# 05_LMS7002M_Misc.net
KiCad netlist of a schematic drawn in Altium Designer
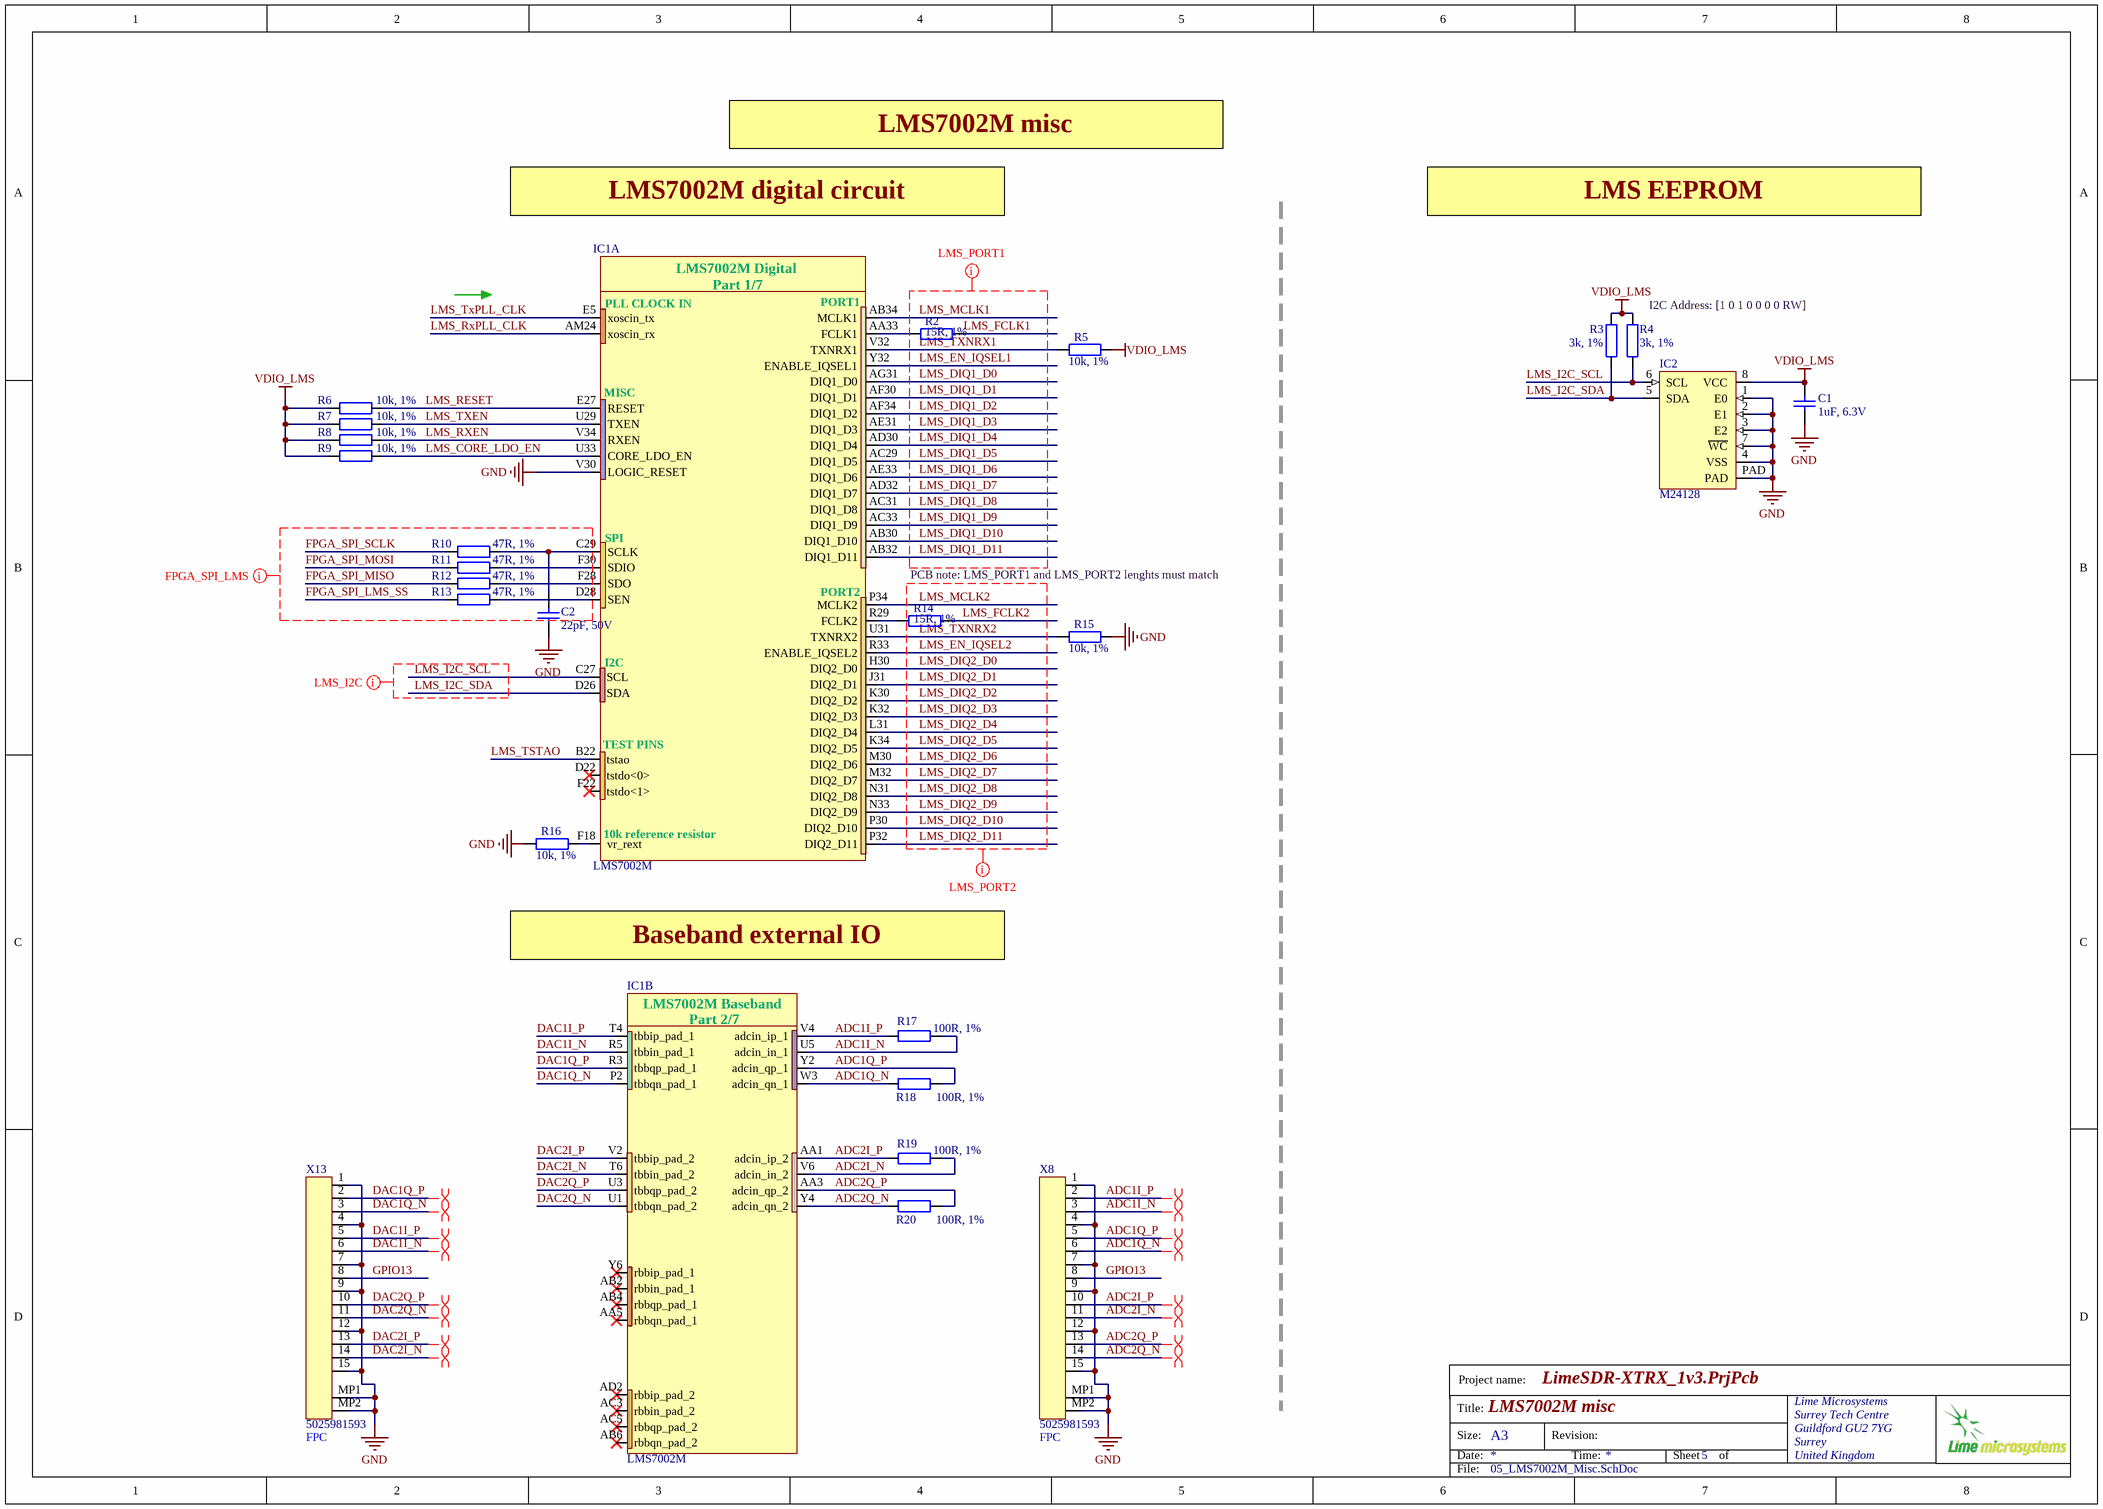
[diagram p0: 05_LMS7002M_Misc.SchDoc]

(export (version "E")
  (design (tool "Eeschema 10.0.6"))
  (components
    (comp (ref "C1")
      (value "1uF, 6.3V")
      (footprint "CAP0201")
      (fields (field (name "TOLERANCE") "±20%") (field (name "MANUFACTURER") "TDK Corporation"))
      (libsource (lib "LimeMicroAltiumLib_schLib") (part "Cap_0402"))
    )
    (comp (ref "C2")
      (value "22pF, 50V")
      (footprint "CAP0201")
      (fields
        (field (name "MANUFACTURER") "Murata")
        (field (name "TOLERANCE") "5%")
        (field (name "VOLTAGE") "50V")
      )
      (libsource (lib "LimeMicroAltiumLib_schLib") (part "Cap_0402"))
    )
    (comp (ref "IC1")
      (value "LMS7002M")
      (footprint "LMS7002M_v5_LESS_SILK")
      (description "Schematic symbol revision 4. Default footprint - 0.31mm pad")
      (fields (field (name "MANUFACTURER") "Lime Microsystems"))
      (libsource (lib "LimeMicroAltiumLib_schLib_r04") (part "LMS7002Mr4"))
    )
    (comp (ref "IC2")
      (value "M24128")
      (footprint "M24128-DFMC6TG")
      (fields (field (name "MANUFACTURER") "STMicroelectronics"))
      (libsource (lib "LimeMicroAltiumLib_schLib") (part "M24128-DFMC6TG"))
    )
    (comp (ref "R2")
      (value "15R, 1%")
      (footprint "RES0201")
      (fields (field (name "MANUFACTURER") "Yageo") (field (name "TOLERANCE") "1%"))
      (libsource (lib "LimeFPGAboard_schLib") (part "Res_0402"))
    )
    (comp (ref "R3")
      (value "3k, 1%")
      (footprint "RES0201")
      (fields (field (name "MANUFACTURER") "Yageo") (field (name "TOLERANCE") "1%"))
      (libsource (lib "LimeFPGAboard_schLib") (part "Res_0402"))
    )
    (comp (ref "R4")
      (value "3k, 1%")
      (footprint "RES0201")
      (fields (field (name "MANUFACTURER") "Yageo") (field (name "TOLERANCE") "1%"))
      (libsource (lib "LimeFPGAboard_schLib") (part "Res_0402"))
    )
    (comp (ref "R5")
      (value "10k, 1%")
      (footprint "RES0201")
      (fields (field (name "MANUFACTURER") "Yageo") (field (name "TOLERANCE") "1%"))
      (libsource (lib "LimeFPGAboard_schLib") (part "Res_0402"))
    )
    (comp (ref "R6")
      (value "10k, 1%")
      (footprint "RES0201")
      (fields (field (name "MANUFACTURER") "Yageo") (field (name "TOLERANCE") "1%"))
      (libsource (lib "LimeFPGAboard_schLib") (part "Res_0402"))
    )
    (comp (ref "R7")
      (value "10k, 1%")
      (footprint "RES0201")
      (fields (field (name "MANUFACTURER") "Yageo") (field (name "TOLERANCE") "1%"))
      (libsource (lib "LimeFPGAboard_schLib") (part "Res_0402"))
    )
    (comp (ref "R8")
      (value "10k, 1%")
      (footprint "RES0201")
      (fields (field (name "MANUFACTURER") "Yageo") (field (name "TOLERANCE") "1%"))
      (libsource (lib "LimeFPGAboard_schLib") (part "Res_0402"))
    )
    (comp (ref "R9")
      (value "10k, 1%")
      (footprint "RES0201")
      (fields (field (name "MANUFACTURER") "Yageo") (field (name "TOLERANCE") "1%"))
      (libsource (lib "LimeFPGAboard_schLib") (part "Res_0402"))
    )
    (comp (ref "R10")
      (value "47R, 1%")
      (footprint "RES0201")
      (fields (field (name "MANUFACTURER") "Yageo") (field (name "TOLERANCE") "1%"))
      (libsource (lib "LimeFPGAboard_schLib") (part "Res_0402"))
    )
    (comp (ref "R11")
      (value "47R, 1%")
      (footprint "RES0201")
      (fields (field (name "MANUFACTURER") "Yageo") (field (name "TOLERANCE") "1%"))
      (libsource (lib "LimeFPGAboard_schLib") (part "Res_0402"))
    )
    (comp (ref "R12")
      (value "47R, 1%")
      (footprint "RES0201")
      (fields (field (name "MANUFACTURER") "Yageo") (field (name "TOLERANCE") "1%"))
      (libsource (lib "LimeFPGAboard_schLib") (part "Res_0402"))
    )
    (comp (ref "R13")
      (value "47R, 1%")
      (footprint "RES0201")
      (fields (field (name "MANUFACTURER") "Yageo") (field (name "TOLERANCE") "1%"))
      (libsource (lib "LimeFPGAboard_schLib") (part "Res_0402"))
    )
    (comp (ref "R14")
      (value "15R, 1%")
      (footprint "RES0201")
      (fields (field (name "MANUFACTURER") "Yageo") (field (name "TOLERANCE") "1%"))
      (libsource (lib "LimeFPGAboard_schLib") (part "Res_0402"))
    )
    (comp (ref "R15")
      (value "10k, 1%")
      (footprint "RES0201")
      (fields (field (name "MANUFACTURER") "Yageo") (field (name "TOLERANCE") "1%"))
      (libsource (lib "LimeFPGAboard_schLib") (part "Res_0402"))
    )
    (comp (ref "R16")
      (value "10k, 1%")
      (footprint "RES0201")
      (fields (field (name "MANUFACTURER") "Yageo") (field (name "TOLERANCE") "1%"))
      (libsource (lib "LimeFPGAboard_schLib") (part "Res_0402"))
    )
    (comp (ref "R17")
      (value "100R, 1%")
      (footprint "RES0201")
      (fields (field (name "MANUFACTURER") "Yageo") (field (name "TOLERANCE") "1%"))
      (libsource (lib "LimeFPGAboard_schLib") (part "Res_0402"))
    )
    (comp (ref "R18")
      (value "100R, 1%")
      (footprint "RES0201")
      (fields (field (name "MANUFACTURER") "Yageo") (field (name "TOLERANCE") "1%"))
      (libsource (lib "LimeFPGAboard_schLib") (part "Res_0402"))
    )
    (comp (ref "R19")
      (value "100R, 1%")
      (footprint "RES0201")
      (fields (field (name "MANUFACTURER") "Yageo") (field (name "TOLERANCE") "1%"))
      (libsource (lib "LimeFPGAboard_schLib") (part "Res_0402"))
    )
    (comp (ref "R20")
      (value "100R, 1%")
      (footprint "RES0201")
      (fields (field (name "MANUFACTURER") "Yageo") (field (name "TOLERANCE") "1%"))
      (libsource (lib "LimeFPGAboard_schLib") (part "Res_0402"))
    )
    (comp (ref "X8")
      (value "5025981593")
      (footprint "5025981593_FPC_connector")
      (fields (field (name "MANUFACTURER") "Molex"))
      (libsource (lib "LimeMicroAltiumLib_schLib_r04") (part "5025981593_FPC_connector"))
    )
    (comp (ref "X13")
      (value "5025981593")
      (footprint "5025981593_FPC_connector")
      (fields (field (name "MANUFACTURER") "Molex"))
      (libsource (lib "LimeMicroAltiumLib_schLib_r04") (part "5025981593_FPC_connector"))
    )
  )
  (nets
    (net (code "1") (name "/ADC1I_N") (class "Default")
      (node (ref "IC1") (pin "U5") (pinfunction "adcin_in_1_U5") (pintype "passive"))
      (node (ref "R17") (pin "2") (pinfunction "2_2") (pintype "passive"))
      (node (ref "X8") (pin "3") (pinfunction "3_3") (pintype "passive"))
    )
    (net (code "2") (name "/ADC1I_P") (class "Default")
      (node (ref "IC1") (pin "V4") (pinfunction "adcin_ip_1_V4") (pintype "passive"))
      (node (ref "R17") (pin "1") (pinfunction "1_1") (pintype "passive"))
      (node (ref "X8") (pin "2") (pinfunction "2_2") (pintype "passive"))
    )
    (net (code "3") (name "/ADC1Q_N") (class "Default")
      (node (ref "IC1") (pin "W3") (pinfunction "adcin_qn_1_W3") (pintype "passive"))
      (node (ref "R18") (pin "1") (pinfunction "1_1") (pintype "passive"))
      (node (ref "X8") (pin "6") (pinfunction "6_6") (pintype "passive"))
    )
    (net (code "4") (name "/ADC1Q_P") (class "Default")
      (node (ref "IC1") (pin "Y2") (pinfunction "adcin_qp_1_Y2") (pintype "passive"))
      (node (ref "R18") (pin "2") (pinfunction "2_2") (pintype "passive"))
      (node (ref "X8") (pin "5") (pinfunction "5_5") (pintype "passive"))
    )
    (net (code "5") (name "/ADC2I_N") (class "Default")
      (node (ref "IC1") (pin "V6") (pinfunction "adcin_in_2_V6") (pintype "passive"))
      (node (ref "R19") (pin "2") (pinfunction "2_2") (pintype "passive"))
      (node (ref "X8") (pin "11") (pinfunction "11_11") (pintype "passive"))
    )
    (net (code "6") (name "/ADC2I_P") (class "Default")
      (node (ref "IC1") (pin "AA1") (pinfunction "adcin_ip_2_AA1") (pintype "passive"))
      (node (ref "R19") (pin "1") (pinfunction "1_1") (pintype "passive"))
      (node (ref "X8") (pin "10") (pinfunction "10_10") (pintype "passive"))
    )
    (net (code "7") (name "/ADC2Q_N") (class "Default")
      (node (ref "IC1") (pin "Y4") (pinfunction "adcin_qn_2_Y4") (pintype "passive"))
      (node (ref "R20") (pin "1") (pinfunction "1_1") (pintype "passive"))
      (node (ref "X8") (pin "14") (pinfunction "14_14") (pintype "passive"))
    )
    (net (code "8") (name "/ADC2Q_P") (class "Default")
      (node (ref "IC1") (pin "AA3") (pinfunction "adcin_qp_2_AA3") (pintype "passive"))
      (node (ref "R20") (pin "2") (pinfunction "2_2") (pintype "passive"))
      (node (ref "X8") (pin "13") (pinfunction "13_13") (pintype "passive"))
    )
    (net (code "9") (name "/DAC1I_N") (class "Default")
      (node (ref "IC1") (pin "R5") (pinfunction "tbbin_pad_1_R5") (pintype "passive"))
      (node (ref "X13") (pin "6") (pinfunction "6_6") (pintype "passive"))
    )
    (net (code "10") (name "/DAC1I_P") (class "Default")
      (node (ref "IC1") (pin "T4") (pinfunction "tbbip_pad_1_T4") (pintype "passive"))
      (node (ref "X13") (pin "5") (pinfunction "5_5") (pintype "passive"))
    )
    (net (code "11") (name "/DAC1Q_N") (class "Default")
      (node (ref "IC1") (pin "P2") (pinfunction "tbbqn_pad_1_P2") (pintype "passive"))
      (node (ref "X13") (pin "3") (pinfunction "3_3") (pintype "passive"))
    )
    (net (code "12") (name "/DAC1Q_P") (class "Default")
      (node (ref "IC1") (pin "R3") (pinfunction "tbbqp_pad_1_R3") (pintype "passive"))
      (node (ref "X13") (pin "2") (pinfunction "2_2") (pintype "passive"))
    )
    (net (code "13") (name "/DAC2I_N") (class "Default")
      (node (ref "IC1") (pin "T6") (pinfunction "tbbin_pad_2_T6") (pintype "passive"))
      (node (ref "X13") (pin "14") (pinfunction "14_14") (pintype "passive"))
    )
    (net (code "14") (name "/DAC2I_P") (class "Default")
      (node (ref "IC1") (pin "V2") (pinfunction "tbbip_pad_2_V2") (pintype "passive"))
      (node (ref "X13") (pin "13") (pinfunction "13_13") (pintype "passive"))
    )
    (net (code "15") (name "/DAC2Q_N") (class "Default")
      (node (ref "IC1") (pin "U1") (pinfunction "tbbqn_pad_2_U1") (pintype "passive"))
      (node (ref "X13") (pin "11") (pinfunction "11_11") (pintype "passive"))
    )
    (net (code "16") (name "/DAC2Q_P") (class "Default")
      (node (ref "IC1") (pin "U3") (pinfunction "tbbqp_pad_2_U3") (pintype "passive"))
      (node (ref "X13") (pin "10") (pinfunction "10_10") (pintype "passive"))
    )
    (net (code "17") (name "/FPGA_SPI_LMS_SS") (class "Default")
      (node (ref "R13") (pin "2") (pinfunction "2_2") (pintype "passive"))
    )
    (net (code "18") (name "/FPGA_SPI_MISO") (class "Default")
      (node (ref "R12") (pin "2") (pinfunction "2_2") (pintype "passive"))
    )
    (net (code "19") (name "/FPGA_SPI_MOSI") (class "Default")
      (node (ref "R11") (pin "2") (pinfunction "2_2") (pintype "passive"))
    )
    (net (code "20") (name "/FPGA_SPI_SCLK") (class "Default")
      (node (ref "R10") (pin "2") (pinfunction "2_2") (pintype "passive"))
    )
    (net (code "21") (name "/GPIO13") (class "Default")
      (node (ref "X13") (pin "8") (pinfunction "8_8") (pintype "passive"))
      (node (ref "X8") (pin "8") (pinfunction "8_8") (pintype "passive"))
    )
    (net (code "22") (name "/LMS_CORE_LDO_EN") (class "Default")
      (node (ref "IC1") (pin "U33") (pinfunction "CORE_LDO_EN_U33") (pintype "passive"))
      (node (ref "R9") (pin "1") (pinfunction "1_1") (pintype "passive"))
    )
    (net (code "23") (name "/LMS_DIQ1_D0") (class "Default")
      (node (ref "IC1") (pin "AG31") (pinfunction "DIQ1_D0_AG31") (pintype "passive"))
    )
    (net (code "24") (name "/LMS_DIQ1_D1") (class "Default")
      (node (ref "IC1") (pin "AF30") (pinfunction "DIQ1_D1_AF30") (pintype "passive"))
    )
    (net (code "25") (name "/LMS_DIQ1_D2") (class "Default")
      (node (ref "IC1") (pin "AF34") (pinfunction "DIQ1_D2_AF34") (pintype "passive"))
    )
    (net (code "26") (name "/LMS_DIQ1_D3") (class "Default")
      (node (ref "IC1") (pin "AE31") (pinfunction "DIQ1_D3_AE31") (pintype "passive"))
    )
    (net (code "27") (name "/LMS_DIQ1_D4") (class "Default")
      (node (ref "IC1") (pin "AD30") (pinfunction "DIQ1_D4_AD30") (pintype "passive"))
    )
    (net (code "28") (name "/LMS_DIQ1_D5") (class "Default")
      (node (ref "IC1") (pin "AC29") (pinfunction "DIQ1_D5_AC29") (pintype "passive"))
    )
    (net (code "29") (name "/LMS_DIQ1_D6") (class "Default")
      (node (ref "IC1") (pin "AE33") (pinfunction "DIQ1_D6_AE33") (pintype "passive"))
    )
    (net (code "30") (name "/LMS_DIQ1_D7") (class "Default")
      (node (ref "IC1") (pin "AD32") (pinfunction "DIQ1_D7_AD32") (pintype "passive"))
    )
    (net (code "31") (name "/LMS_DIQ1_D8") (class "Default")
      (node (ref "IC1") (pin "AC31") (pinfunction "DIQ1_D8_AC31") (pintype "passive"))
    )
    (net (code "32") (name "/LMS_DIQ1_D9") (class "Default")
      (node (ref "IC1") (pin "AC33") (pinfunction "DIQ1_D9_AC33") (pintype "passive"))
    )
    (net (code "33") (name "/LMS_DIQ1_D10") (class "Default")
      (node (ref "IC1") (pin "AB30") (pinfunction "DIQ1_D10_AB30") (pintype "passive"))
    )
    (net (code "34") (name "/LMS_DIQ1_D11") (class "Default")
      (node (ref "IC1") (pin "AB32") (pinfunction "DIQ1_D11_AB32") (pintype "passive"))
    )
    (net (code "35") (name "/LMS_DIQ2_D0") (class "Default")
      (node (ref "IC1") (pin "H30") (pinfunction "DIQ2_D0_H30") (pintype "passive"))
    )
    (net (code "36") (name "/LMS_DIQ2_D1") (class "Default")
      (node (ref "IC1") (pin "J31") (pinfunction "DIQ2_D1_J31") (pintype "passive"))
    )
    (net (code "37") (name "/LMS_DIQ2_D2") (class "Default")
      (node (ref "IC1") (pin "K30") (pinfunction "DIQ2_D2_K30") (pintype "passive"))
    )
    (net (code "38") (name "/LMS_DIQ2_D3") (class "Default")
      (node (ref "IC1") (pin "K32") (pinfunction "DIQ2_D3_K32") (pintype "passive"))
    )
    (net (code "39") (name "/LMS_DIQ2_D4") (class "Default")
      (node (ref "IC1") (pin "L31") (pinfunction "DIQ2_D4_L31") (pintype "passive"))
    )
    (net (code "40") (name "/LMS_DIQ2_D5") (class "Default")
      (node (ref "IC1") (pin "K34") (pinfunction "DIQ2_D5_K34") (pintype "passive"))
    )
    (net (code "41") (name "/LMS_DIQ2_D6") (class "Default")
      (node (ref "IC1") (pin "M30") (pinfunction "DIQ2_D6_M30") (pintype "passive"))
    )
    (net (code "42") (name "/LMS_DIQ2_D7") (class "Default")
      (node (ref "IC1") (pin "M32") (pinfunction "DIQ2_D7_M32") (pintype "passive"))
    )
    (net (code "43") (name "/LMS_DIQ2_D8") (class "Default")
      (node (ref "IC1") (pin "N31") (pinfunction "DIQ2_D8_N31") (pintype "passive"))
    )
    (net (code "44") (name "/LMS_DIQ2_D9") (class "Default")
      (node (ref "IC1") (pin "N33") (pinfunction "DIQ2_D9_N33") (pintype "passive"))
    )
    (net (code "45") (name "/LMS_DIQ2_D10") (class "Default")
      (node (ref "IC1") (pin "P30") (pinfunction "DIQ2_D10_P30") (pintype "passive"))
    )
    (net (code "46") (name "/LMS_DIQ2_D11") (class "Default")
      (node (ref "IC1") (pin "P32") (pinfunction "DIQ2_D11_P32") (pintype "passive"))
    )
    (net (code "47") (name "/LMS_EN_IQSEL1") (class "Default")
      (node (ref "IC1") (pin "Y32") (pinfunction "ENABLE_IQSEL1_Y32") (pintype "passive"))
    )
    (net (code "48") (name "/LMS_EN_IQSEL2") (class "Default")
      (node (ref "IC1") (pin "R33") (pinfunction "ENABLE_IQSEL2_R33") (pintype "passive"))
    )
    (net (code "49") (name "/LMS_FCLK1") (class "Default")
      (node (ref "R2") (pin "1") (pinfunction "1_1") (pintype "passive"))
    )
    (net (code "50") (name "/LMS_FCLK2") (class "Default")
      (node (ref "R14") (pin "1") (pinfunction "1_1") (pintype "passive"))
    )
    (net (code "51") (name "/LMS_I2C_SCL") (class "Default")
      (node (ref "IC1") (pin "C27") (pinfunction "SCL_C27") (pintype "passive"))
      (node (ref "IC2") (pin "6") (pinfunction "SCL_6") (pintype "input"))
      (node (ref "R4") (pin "1") (pinfunction "1_1") (pintype "passive"))
    )
    (net (code "52") (name "/LMS_I2C_SDA") (class "Default")
      (node (ref "IC1") (pin "D26") (pinfunction "SDA_D26") (pintype "passive"))
      (node (ref "IC2") (pin "5") (pinfunction "SDA_5") (pintype "bidirectional"))
      (node (ref "R3") (pin "1") (pinfunction "1_1") (pintype "passive"))
    )
    (net (code "53") (name "/LMS_MCLK1") (class "Default")
      (node (ref "IC1") (pin "AB34") (pinfunction "MCLK1_AB34") (pintype "passive"))
    )
    (net (code "54") (name "/LMS_MCLK2") (class "Default")
      (node (ref "IC1") (pin "P34") (pinfunction "MCLK2_P34") (pintype "passive"))
    )
    (net (code "55") (name "/LMS_RESET") (class "Default")
      (node (ref "IC1") (pin "E27") (pinfunction "RESET_E27") (pintype "passive"))
      (node (ref "R6") (pin "1") (pinfunction "1_1") (pintype "passive"))
    )
    (net (code "56") (name "/LMS_RXEN") (class "Default")
      (node (ref "IC1") (pin "V34") (pinfunction "RXEN_V34") (pintype "passive"))
      (node (ref "R8") (pin "1") (pinfunction "1_1") (pintype "passive"))
    )
    (net (code "57") (name "/LMS_RxPLL_CLK") (class "Default")
      (node (ref "IC1") (pin "AM24") (pinfunction "xoscin_rx_AM24") (pintype "passive"))
    )
    (net (code "58") (name "/LMS_TSTAO") (class "Default")
      (node (ref "IC1") (pin "B22") (pinfunction "tstao_B22") (pintype "passive"))
    )
    (net (code "59") (name "/LMS_TXEN") (class "Default")
      (node (ref "IC1") (pin "U29") (pinfunction "TXEN_U29") (pintype "passive"))
      (node (ref "R7") (pin "1") (pinfunction "1_1") (pintype "passive"))
    )
    (net (code "60") (name "/LMS_TXNRX1") (class "Default")
      (node (ref "IC1") (pin "V32") (pinfunction "TXNRX1_V32") (pintype "passive"))
      (node (ref "R5") (pin "2") (pinfunction "2_2") (pintype "passive"))
    )
    (net (code "61") (name "/LMS_TXNRX2") (class "Default")
      (node (ref "IC1") (pin "U31") (pinfunction "TXNRX2_U31") (pintype "passive"))
      (node (ref "R15") (pin "2") (pinfunction "2_2") (pintype "passive"))
    )
    (net (code "62") (name "/LMS_TxPLL_CLK") (class "Default")
      (node (ref "IC1") (pin "E5") (pinfunction "xoscin_tx_E5") (pintype "passive"))
    )
    (net (code "63") (name "GND") (class "Default")
      (node (ref "C1") (pin "2") (pinfunction "2_2") (pintype "passive"))
      (node (ref "C2") (pin "1") (pinfunction "1_1") (pintype "passive"))
      (node (ref "IC1") (pin "V30") (pinfunction "LOGIC_RESET_V30") (pintype "passive"))
      (node (ref "IC2") (pin "1") (pinfunction "E0_1") (pintype "input"))
      (node (ref "IC2") (pin "2") (pinfunction "E1_2") (pintype "input"))
      (node (ref "IC2") (pin "3") (pinfunction "E2_3") (pintype "input"))
      (node (ref "IC2") (pin "4") (pinfunction "VSS_4") (pintype "power_in"))
      (node (ref "IC2") (pin "7") (pinfunction "~{WC}_7") (pintype "input"))
      (node (ref "IC2") (pin "PAD") (pinfunction "PAD_PAD") (pintype "power_in"))
      (node (ref "R15") (pin "1") (pinfunction "1_1") (pintype "passive"))
      (node (ref "R16") (pin "2") (pinfunction "2_2") (pintype "passive"))
      (node (ref "X13") (pin "1") (pinfunction "1_1") (pintype "passive"))
      (node (ref "X13") (pin "12") (pinfunction "12_12") (pintype "passive"))
      (node (ref "X13") (pin "15") (pinfunction "15_15") (pintype "passive"))
      (node (ref "X13") (pin "4") (pinfunction "4_4") (pintype "passive"))
      (node (ref "X13") (pin "7") (pinfunction "7_7") (pintype "passive"))
      (node (ref "X13") (pin "9") (pinfunction "9_9") (pintype "passive"))
      (node (ref "X13") (pin "MP1") (pinfunction "MP1_MP1") (pintype "passive"))
      (node (ref "X13") (pin "MP2") (pinfunction "MP2_MP2") (pintype "passive"))
      (node (ref "X8") (pin "1") (pinfunction "1_1") (pintype "passive"))
      (node (ref "X8") (pin "12") (pinfunction "12_12") (pintype "passive"))
      (node (ref "X8") (pin "15") (pinfunction "15_15") (pintype "passive"))
      (node (ref "X8") (pin "4") (pinfunction "4_4") (pintype "passive"))
      (node (ref "X8") (pin "7") (pinfunction "7_7") (pintype "passive"))
      (node (ref "X8") (pin "9") (pinfunction "9_9") (pintype "passive"))
      (node (ref "X8") (pin "MP1") (pinfunction "MP1_MP1") (pintype "passive"))
      (node (ref "X8") (pin "MP2") (pinfunction "MP2_MP2") (pintype "passive"))
    )
    (net (code "64") (name "Net-(IC1A-FCLK1)") (class "Default")
      (node (ref "IC1") (pin "AA33") (pinfunction "FCLK1_AA33") (pintype "passive"))
      (node (ref "R2") (pin "2") (pinfunction "2_2") (pintype "passive"))
    )
    (net (code "65") (name "Net-(IC1A-FCLK2)") (class "Default")
      (node (ref "IC1") (pin "R29") (pinfunction "FCLK2_R29") (pintype "passive"))
      (node (ref "R14") (pin "2") (pinfunction "2_2") (pintype "passive"))
    )
    (net (code "66") (name "Net-(IC1A-SCLK)") (class "Default")
      (node (ref "C2") (pin "2") (pinfunction "2_2") (pintype "passive"))
      (node (ref "IC1") (pin "C29") (pinfunction "SCLK_C29") (pintype "passive"))
      (node (ref "R10") (pin "1") (pinfunction "1_1") (pintype "passive"))
    )
    (net (code "67") (name "Net-(IC1A-SDIO)") (class "Default")
      (node (ref "IC1") (pin "F30") (pinfunction "SDIO_F30") (pintype "passive"))
      (node (ref "R11") (pin "1") (pinfunction "1_1") (pintype "passive"))
    )
    (net (code "68") (name "Net-(IC1A-SDO)") (class "Default")
      (node (ref "IC1") (pin "F28") (pinfunction "SDO_F28") (pintype "passive"))
      (node (ref "R12") (pin "1") (pinfunction "1_1") (pintype "passive"))
    )
    (net (code "69") (name "Net-(IC1A-SEN)") (class "Default")
      (node (ref "IC1") (pin "D28") (pinfunction "SEN_D28") (pintype "passive"))
      (node (ref "R13") (pin "1") (pinfunction "1_1") (pintype "passive"))
    )
    (net (code "70") (name "Net-(IC1A-vr_rext)") (class "Default")
      (node (ref "IC1") (pin "F18") (pinfunction "vr_rext_F18") (pintype "passive"))
      (node (ref "R16") (pin "1") (pinfunction "1_1") (pintype "passive"))
    )
    (net (code "71") (name "VDIO_LMS") (class "Default")
      (node (ref "C1") (pin "1") (pinfunction "1_1") (pintype "passive"))
      (node (ref "IC2") (pin "8") (pinfunction "VCC_8") (pintype "power_in"))
      (node (ref "R3") (pin "2") (pinfunction "2_2") (pintype "passive"))
      (node (ref "R4") (pin "2") (pinfunction "2_2") (pintype "passive"))
      (node (ref "R5") (pin "1") (pinfunction "1_1") (pintype "passive"))
      (node (ref "R6") (pin "2") (pinfunction "2_2") (pintype "passive"))
      (node (ref "R7") (pin "2") (pinfunction "2_2") (pintype "passive"))
      (node (ref "R8") (pin "2") (pinfunction "2_2") (pintype "passive"))
      (node (ref "R9") (pin "2") (pinfunction "2_2") (pintype "passive"))
    )
    (net (code "72") (name "unconnected-(IC1A-tstdo<0>-PadD22)") (class "Default")
      (node (ref "IC1") (pin "D22") (pinfunction "tstdo<0>_D22") (pintype "passive+no_connect"))
    )
    (net (code "73") (name "unconnected-(IC1A-tstdo<1>-PadF22)") (class "Default")
      (node (ref "IC1") (pin "F22") (pinfunction "tstdo<1>_F22") (pintype "passive+no_connect"))
    )
    (net (code "74") (name "unconnected-(IC1B-rbbin_pad_1-PadAB2)") (class "Default")
      (node (ref "IC1") (pin "AB2") (pinfunction "rbbin_pad_1_AB2") (pintype "passive+no_connect"))
    )
    (net (code "75") (name "unconnected-(IC1B-rbbin_pad_2-PadAC3)") (class "Default")
      (node (ref "IC1") (pin "AC3") (pinfunction "rbbin_pad_2_AC3") (pintype "passive+no_connect"))
    )
    (net (code "76") (name "unconnected-(IC1B-rbbip_pad_1-PadY6)") (class "Default")
      (node (ref "IC1") (pin "Y6") (pinfunction "rbbip_pad_1_Y6") (pintype "passive+no_connect"))
    )
    (net (code "77") (name "unconnected-(IC1B-rbbip_pad_2-PadAD2)") (class "Default")
      (node (ref "IC1") (pin "AD2") (pinfunction "rbbip_pad_2_AD2") (pintype "passive+no_connect"))
    )
    (net (code "78") (name "unconnected-(IC1B-rbbqn_pad_1-PadAA5)") (class "Default")
      (node (ref "IC1") (pin "AA5") (pinfunction "rbbqn_pad_1_AA5") (pintype "passive+no_connect"))
    )
    (net (code "79") (name "unconnected-(IC1B-rbbqn_pad_2-PadAB6)") (class "Default")
      (node (ref "IC1") (pin "AB6") (pinfunction "rbbqn_pad_2_AB6") (pintype "passive+no_connect"))
    )
    (net (code "80") (name "unconnected-(IC1B-rbbqp_pad_1-PadAB4)") (class "Default")
      (node (ref "IC1") (pin "AB4") (pinfunction "rbbqp_pad_1_AB4") (pintype "passive+no_connect"))
    )
    (net (code "81") (name "unconnected-(IC1B-rbbqp_pad_2-PadAC5)") (class "Default")
      (node (ref "IC1") (pin "AC5") (pinfunction "rbbqp_pad_2_AC5") (pintype "passive+no_connect"))
    )
  )
)
